# PWR_SRC.net
KiCad netlist of a schematic drawn in Altium Designer
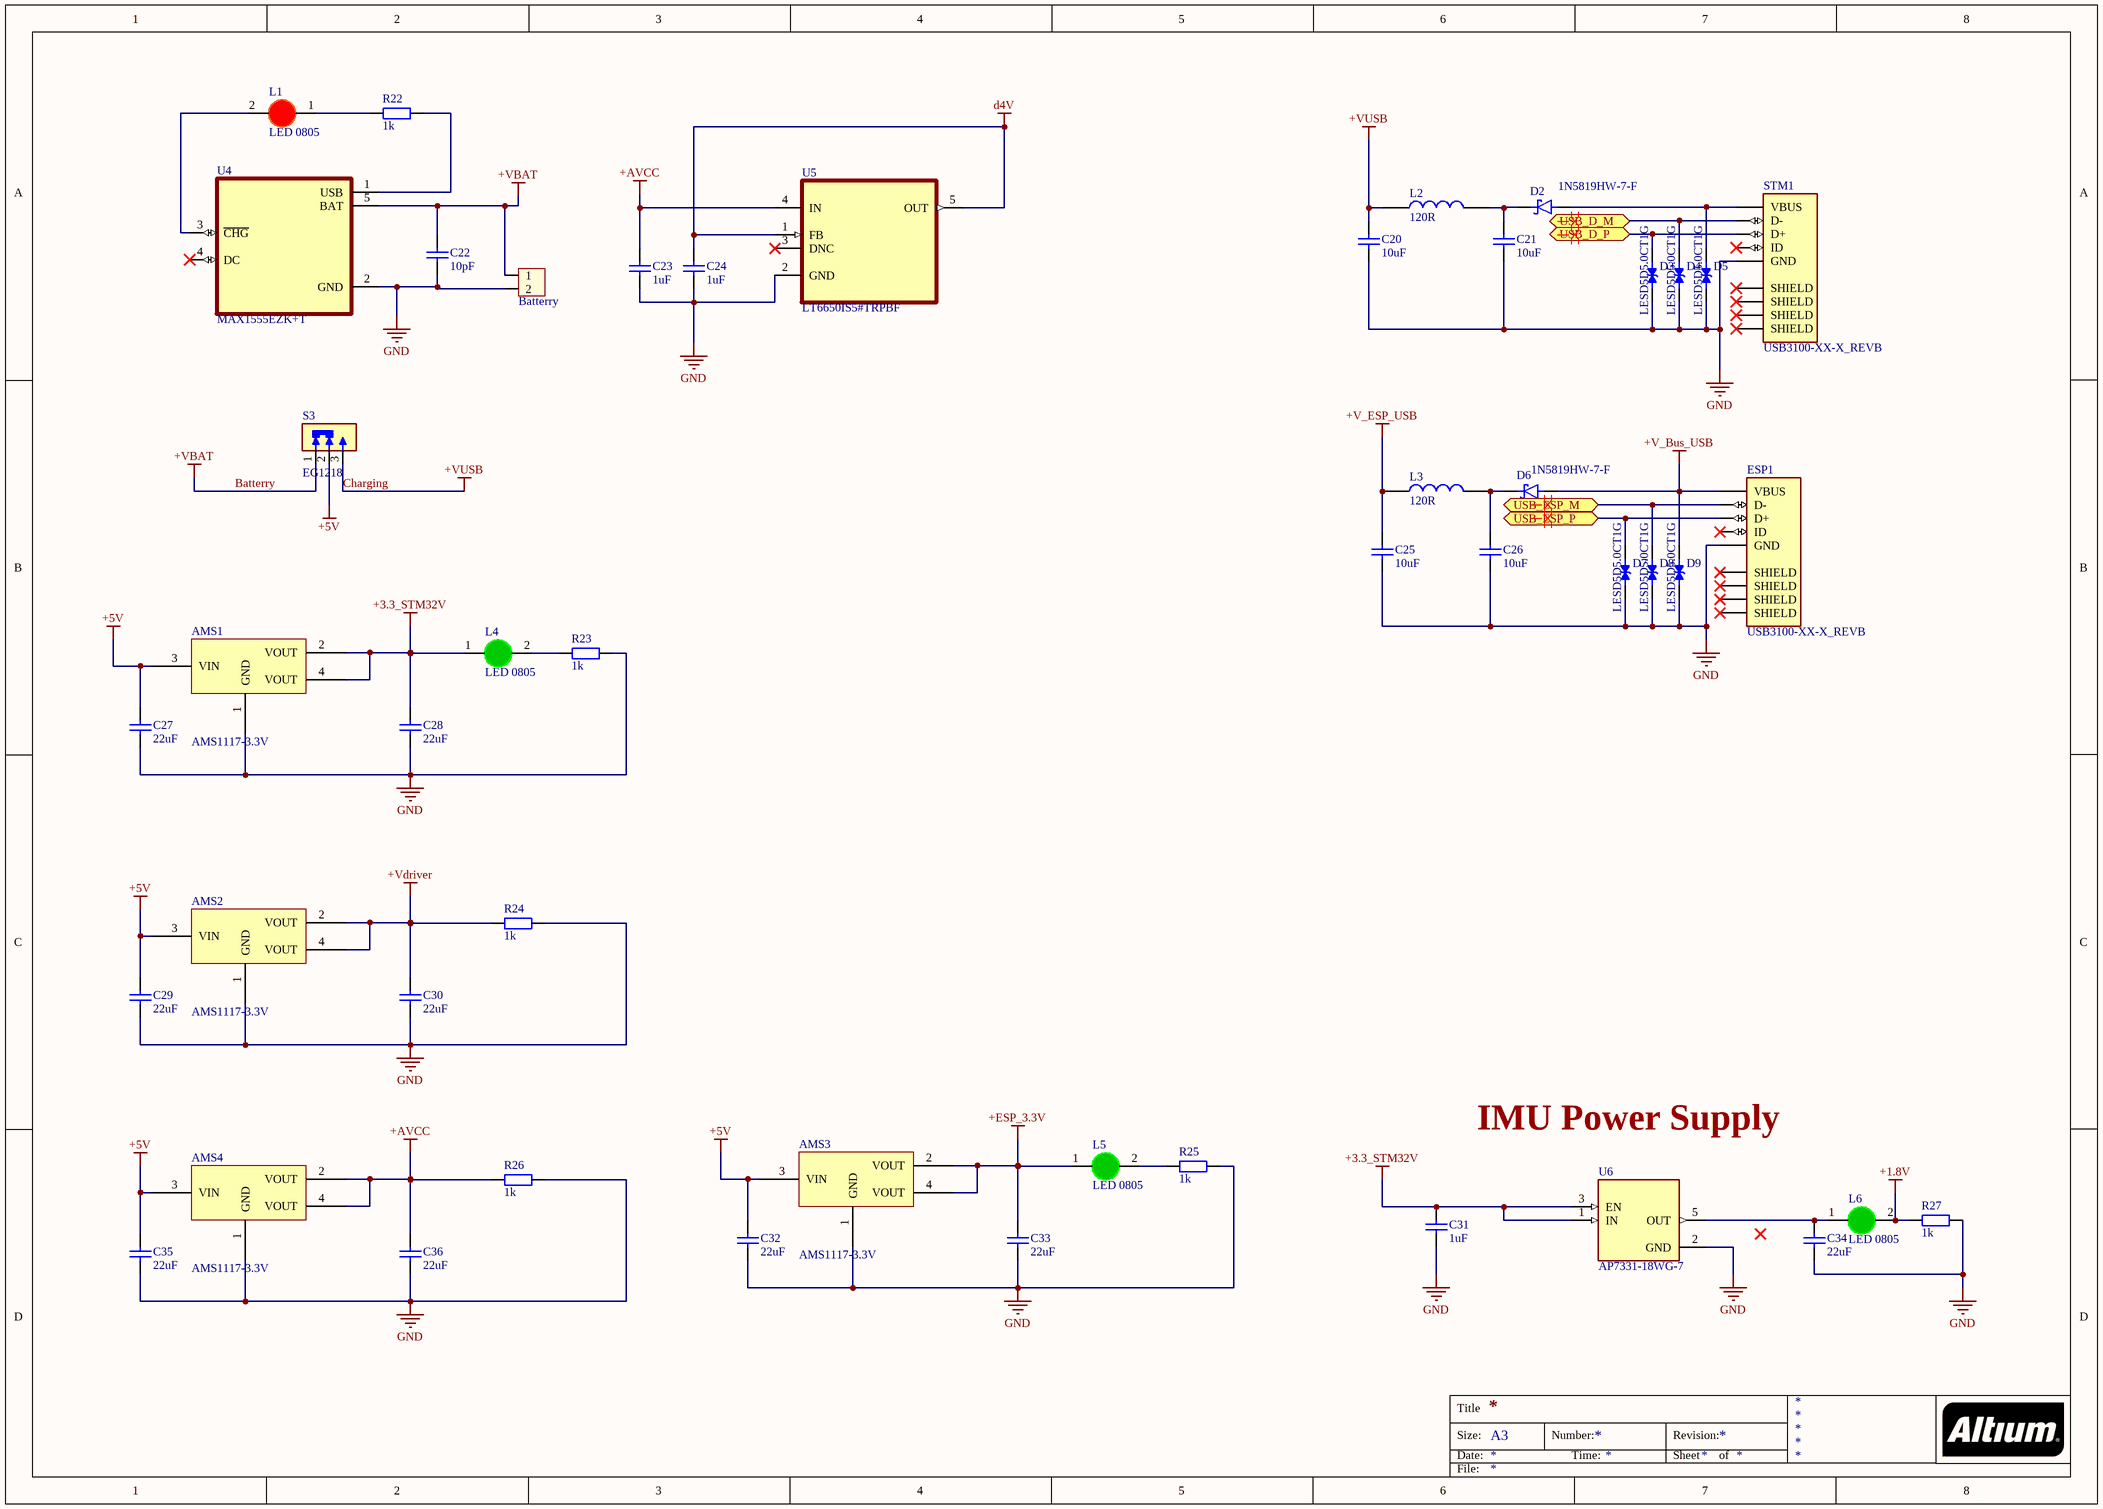
[diagram p0: PWR_SRC.SchDoc]

(export (version "E")
  (design (tool "Eeschema 10.0.6"))
  (components
    (comp (ref "AMS1")
      (value "AMS1117-3.3V")
      (footprint "SOT223")
      (description "Dán")
      (libsource (lib "Altium_Lib_by_KhueNguyenCreator") (part "AMS1117 SMD"))
    )
    (comp (ref "AMS2")
      (value "AMS1117-3.3V")
      (footprint "SOT223")
      (description "Dán")
      (libsource (lib "Altium_Lib_by_KhueNguyenCreator") (part "AMS1117 SMD"))
    )
    (comp (ref "AMS3")
      (value "AMS1117-3.3V")
      (footprint "SOT223")
      (description "Dán")
      (libsource (lib "Altium_Lib_by_KhueNguyenCreator") (part "AMS1117 SMD"))
    )
    (comp (ref "AMS4")
      (value "AMS1117-3.3V")
      (footprint "SOT223")
      (description "Dán")
      (libsource (lib "Altium_Lib_by_KhueNguyenCreator") (part "AMS1117 SMD"))
    )
    (comp (ref "Batterry1")
      (value "Batterry")
      (footprint "XH2.54M-2")
      (description "Cắm")
      (libsource (lib "Altium_Lib_by_KhueNguyenCreator") (part "Header 2P 2.54 Duc Thang"))
    )
    (comp (ref "C20")
      (value "10uF")
      (footprint "tu 0805")
      (description "Dán")
      (libsource (lib "Altium_Lib_by_KhueNguyenCreator") (part "Tu 0805 10pF 50V 10%"))
    )
    (comp (ref "C21")
      (value "10uF")
      (footprint "tu 0805")
      (description "Dán")
      (libsource (lib "Altium_Lib_by_KhueNguyenCreator") (part "Tu 0805 10pF 50V 10%"))
    )
    (comp (ref "C22")
      (value "10pF")
      (footprint "tu 0805")
      (description "Dán")
      (libsource (lib "Altium_Lib_by_KhueNguyenCreator") (part "Tu 0805 10pF 50V 10%"))
    )
    (comp (ref "C23")
      (value "1uF")
      (footprint "tu 0603")
      (description "Dán")
      (libsource (lib "Altium_Lib_by_KhueNguyenCreator") (part "Tu 0603 470pF 50V 10%"))
    )
    (comp (ref "C24")
      (value "1uF")
      (footprint "tu 0603")
      (description "Dán")
      (libsource (lib "Altium_Lib_by_KhueNguyenCreator") (part "Tu 0603 470pF 50V 10%"))
    )
    (comp (ref "C25")
      (value "10uF")
      (footprint "tu 0805")
      (description "Dán")
      (libsource (lib "Altium_Lib_by_KhueNguyenCreator") (part "Tu 0805 10pF 50V 10%"))
    )
    (comp (ref "C26")
      (value "10uF")
      (footprint "tu 0805")
      (description "Dán")
      (libsource (lib "Altium_Lib_by_KhueNguyenCreator") (part "Tu 0805 10pF 50V 10%"))
    )
    (comp (ref "C27")
      (value "22uF")
      (footprint "tu 0805")
      (description "Dán")
      (libsource (lib "Altium_Lib_by_KhueNguyenCreator") (part "Tu 0805 10pF 50V 10%"))
    )
    (comp (ref "C28")
      (value "22uF")
      (footprint "tu 0805")
      (description "Dán")
      (libsource (lib "Altium_Lib_by_KhueNguyenCreator") (part "Tu 0805 10pF 50V 10%"))
    )
    (comp (ref "C29")
      (value "22uF")
      (footprint "tu 0805")
      (description "Dán")
      (libsource (lib "Altium_Lib_by_KhueNguyenCreator") (part "Tu 0805 10pF 50V 10%"))
    )
    (comp (ref "C30")
      (value "22uF")
      (footprint "tu 0805")
      (description "Dán")
      (libsource (lib "Altium_Lib_by_KhueNguyenCreator") (part "Tu 0805 10pF 50V 10%"))
    )
    (comp (ref "C31")
      (value "1uF")
      (footprint "tu 0805")
      (description "Dán")
      (libsource (lib "Altium_Lib_by_KhueNguyenCreator") (part "Tu 0805 106 16V 10%"))
    )
    (comp (ref "C32")
      (value "22uF")
      (footprint "tu 0805")
      (description "Dán")
      (libsource (lib "Altium_Lib_by_KhueNguyenCreator") (part "Tu 0805 10pF 50V 10%"))
    )
    (comp (ref "C33")
      (value "22uF")
      (footprint "tu 0805")
      (description "Dán")
      (libsource (lib "Altium_Lib_by_KhueNguyenCreator") (part "Tu 0805 10pF 50V 10%"))
    )
    (comp (ref "C34")
      (value "22uF")
      (footprint "tu 0805")
      (description "Dán")
      (libsource (lib "Altium_Lib_by_KhueNguyenCreator") (part "Tu 0805 10pF 50V 10%"))
    )
    (comp (ref "C35")
      (value "22uF")
      (footprint "tu 0805")
      (description "Dán")
      (libsource (lib "Altium_Lib_by_KhueNguyenCreator") (part "Tu 0805 10pF 50V 10%"))
    )
    (comp (ref "C36")
      (value "22uF")
      (footprint "tu 0805")
      (description "Dán")
      (libsource (lib "Altium_Lib_by_KhueNguyenCreator") (part "Tu 0805 10pF 50V 10%"))
    )
    (comp (ref "D2")
      (value "1N5819HW-7-F")
      (footprint "1N5819HW-7-F:SOD3715X145N")
      (description "1N5819HW Series 40 V 1 A Surface Mount Schottky Barrier Rectifier - SOD-123")
      (fields (field (name "MF") "{'manufacturer': u'Diodes Inc.'}"))
      (libsource (lib "*") (part "1N5819HW-7-F"))
    )
    (comp (ref "D3")
      (value "LESD5D5.0CT1G")
      (footprint "LESD5D5.0CT1G:TVS_LESD5D5.0CT1G")
      (fields (field (name "MF") "{'manufacturer': u'Leshan Radio Co.'}"))
      (libsource (lib "*") (part "LESD5D5.0CT1G"))
    )
    (comp (ref "D4")
      (value "LESD5D5.0CT1G")
      (footprint "LESD5D5.0CT1G:TVS_LESD5D5.0CT1G")
      (fields (field (name "MF") "{'manufacturer': u'Leshan Radio Co.'}"))
      (libsource (lib "*") (part "LESD5D5.0CT1G"))
    )
    (comp (ref "D5")
      (value "LESD5D5.0CT1G")
      (footprint "LESD5D5.0CT1G:TVS_LESD5D5.0CT1G")
      (fields (field (name "MF") "{'manufacturer': u'Leshan Radio Co.'}"))
      (libsource (lib "*") (part "LESD5D5.0CT1G"))
    )
    (comp (ref "D6")
      (value "1N5819HW-7-F")
      (footprint "1N5819HW-7-F:SOD3715X145N")
      (description "1N5819HW Series 40 V 1 A Surface Mount Schottky Barrier Rectifier - SOD-123")
      (fields (field (name "MF") "{'manufacturer': u'Diodes Inc.'}"))
      (libsource (lib "*") (part "1N5819HW-7-F"))
    )
    (comp (ref "D7")
      (value "LESD5D5.0CT1G")
      (footprint "LESD5D5.0CT1G:TVS_LESD5D5.0CT1G")
      (fields (field (name "MF") "{'manufacturer': u'Leshan Radio Co.'}"))
      (libsource (lib "*") (part "LESD5D5.0CT1G"))
    )
    (comp (ref "D8")
      (value "LESD5D5.0CT1G")
      (footprint "LESD5D5.0CT1G:TVS_LESD5D5.0CT1G")
      (fields (field (name "MF") "{'manufacturer': u'Leshan Radio Co.'}"))
      (libsource (lib "*") (part "LESD5D5.0CT1G"))
    )
    (comp (ref "D9")
      (value "LESD5D5.0CT1G")
      (footprint "LESD5D5.0CT1G:TVS_LESD5D5.0CT1G")
      (fields (field (name "MF") "{'manufacturer': u'Leshan Radio Co.'}"))
      (libsource (lib "*") (part "LESD5D5.0CT1G"))
    )
    (comp (ref "ESP1")
      (value "USB3100-XX-X_REVB")
      (footprint "USB3100-30-A:GCT_USB3100-XX-X_REVB")
      (description "Micro USB Receptacle, Type B, Surface Mount, Horizontal, Top (Reverse) Mount, without Peg")
      (fields (field (name "MF") "{'manufacturer': u'Global Connector Technology'}"))
      (libsource (lib "*") (part "USB3100-XX-X_REVB"))
    )
    (comp (ref "L1")
      (value "LED 0805")
      (footprint "LED-1206-Red")
      (description "Dán")
      (libsource (lib "Altium_Lib_by_KhueNguyenCreator") (part "LED 1206 Do"))
    )
    (comp (ref "L2")
      (value "120R")
      (footprint "IND-0603 (1608)")
      (description "IND-FERRITE BEAD 23 OHM  4A 0603 1LN")
      (fields (field (name "MPN") "FBMJ1608HM230NT"))
      (libsource (lib "BYTECH_HW_LIB_2019 (1)") (part "FBMJ1608HM230NT"))
    )
    (comp (ref "L3")
      (value "120R")
      (footprint "IND-0603 (1608)")
      (description "IND-FERRITE BEAD 23 OHM  4A 0603 1LN")
      (fields (field (name "MPN") "FBMJ1608HM230NT"))
      (libsource (lib "BYTECH_HW_LIB_2019 (1)") (part "FBMJ1608HM230NT"))
    )
    (comp (ref "L4")
      (value "LED 0805")
      (footprint "LED-1206-Green")
      (description "Dán")
      (libsource (lib "Altium_Lib_by_KhueNguyenCreator") (part "LED 1206 Xanh La"))
    )
    (comp (ref "L5")
      (value "LED 0805")
      (footprint "LED-1206-Green")
      (description "Dán")
      (libsource (lib "Altium_Lib_by_KhueNguyenCreator") (part "LED 1206 Xanh La"))
    )
    (comp (ref "L6")
      (value "LED 0805")
      (footprint "LED-1206-Green")
      (description "Dán")
      (libsource (lib "Altium_Lib_by_KhueNguyenCreator") (part "LED 1206 Xanh La"))
    )
    (comp (ref "R22")
      (value "1k")
      (footprint "tro smd 0805")
      (description "Dán")
      (libsource (lib "Altium_Lib_by_KhueNguyenCreator") (part "Tro 0805 1% 1k"))
    )
    (comp (ref "R23")
      (value "1k")
      (footprint "tro smd 0805")
      (description "Dán")
      (libsource (lib "Altium_Lib_by_KhueNguyenCreator") (part "Tro 0805 1% 1k"))
    )
    (comp (ref "R24")
      (value "1k")
      (footprint "tro smd 0805")
      (description "Dán")
      (libsource (lib "Altium_Lib_by_KhueNguyenCreator") (part "Tro 0805 1% 1k"))
    )
    (comp (ref "R25")
      (value "1k")
      (footprint "tro smd 0805")
      (description "Dán")
      (libsource (lib "Altium_Lib_by_KhueNguyenCreator") (part "Tro 0805 1% 1k"))
    )
    (comp (ref "R26")
      (value "1k")
      (footprint "tro smd 0805")
      (description "Dán")
      (libsource (lib "Altium_Lib_by_KhueNguyenCreator") (part "Tro 0805 1% 1k"))
    )
    (comp (ref "R27")
      (value "1k")
      (footprint "tro smd 0805")
      (description "Dán")
      (libsource (lib "Altium_Lib_by_KhueNguyenCreator") (part "Tro 0805 1% 1k"))
    )
    (comp (ref "S3")
      (value "EG1218")
      (footprint "SW_EG1218")
      (description "Slide Switch, EG Series, SPDT, Non-Shorting, ON-ON, 200mA DC, 30VDC, PC Pin ¦ E-Switch EG1218")
      (fields (field (name "MF") "E-Switch"))
      (libsource (lib "EG1218") (part "EG1218"))
    )
    (comp (ref "STM1")
      (value "USB3100-XX-X_REVB")
      (footprint "USB3100-30-A:GCT_USB3100-XX-X_REVB")
      (description "Micro USB Receptacle, Type B, Surface Mount, Horizontal, Top (Reverse) Mount, without Peg")
      (fields (field (name "MF") "{'manufacturer': u'Global Connector Technology'}"))
      (libsource (lib "*") (part "USB3100-XX-X_REVB"))
    )
    (comp (ref "U4")
      (value "MAX1555EZK+T")
      (footprint "MAX1555EZK:SOT95P275X110-5N")
      (fields (field (name "MF") "{'manufacturer': u'Analog Devices'}") (field (name "MP") "MAX1555EZK+"))
      (libsource (lib "*") (part "MAX1555EZK+T"))
    )
    (comp (ref "U5")
      (value "LT6650IS5#TRPBF")
      (footprint "LT6650IS5#TRPBF:SOT95P280X100-5N")
      (description "Micropower, 400mV Reference with Rail-to-Rail Buffer Amplifier")
      (fields (field (name "MF") "{'manufacturer': u'Analog Devices'}"))
      (libsource (lib "*") (part "LT6650IS5#TRPBF"))
    )
    (comp (ref "U6")
      (value "AP7331-18WG-7")
      (footprint "AP7331-18WG-7:SOT95P285X145-5N")
      (description "LDO Regulator Pos 1.8V 0.3A 5-Pin SOT-25 T/R")
      (fields (field (name "MF") "{'manufacturer': u'Diodes Inc.'}"))
      (libsource (lib "*") (part "AP7331-18WG-7"))
    )
  )
  (nets
    (net (code "1") (name "+1.8V") (class "Default")
      (node (ref "L6") (pin "2") (pinfunction "K_2") (pintype "passive"))
      (node (ref "R27") (pin "1") (pinfunction "1_1") (pintype "passive"))
    )
    (net (code "2") (name "+3.3_STM32V") (class "Default")
      (node (ref "AMS1") (pin "2") (pinfunction "VOUT_2") (pintype "passive"))
      (node (ref "AMS1") (pin "4") (pinfunction "VOUT_4") (pintype "passive"))
      (node (ref "C28") (pin "1") (pinfunction "1_1") (pintype "passive"))
      (node (ref "C31") (pin "1") (pinfunction "1_1") (pintype "passive"))
      (node (ref "L4") (pin "1") (pinfunction "A_1") (pintype "passive"))
      (node (ref "U6") (pin "1") (pinfunction "IN_1") (pintype "input"))
      (node (ref "U6") (pin "3") (pinfunction "EN_3") (pintype "input"))
    )
    (net (code "3") (name "+5V") (class "Default")
      (node (ref "AMS1") (pin "3") (pinfunction "VIN_3") (pintype "passive"))
      (node (ref "AMS2") (pin "3") (pinfunction "VIN_3") (pintype "passive"))
      (node (ref "AMS3") (pin "3") (pinfunction "VIN_3") (pintype "passive"))
      (node (ref "AMS4") (pin "3") (pinfunction "VIN_3") (pintype "passive"))
      (node (ref "C27") (pin "1") (pinfunction "1_1") (pintype "passive"))
      (node (ref "C29") (pin "1") (pinfunction "1_1") (pintype "passive"))
      (node (ref "C32") (pin "1") (pinfunction "1_1") (pintype "passive"))
      (node (ref "C35") (pin "1") (pinfunction "1_1") (pintype "passive"))
      (node (ref "S3") (pin "2") (pinfunction "COM_2") (pintype "passive"))
    )
    (net (code "4") (name "+AVCC") (class "Default")
      (node (ref "AMS4") (pin "2") (pinfunction "VOUT_2") (pintype "passive"))
      (node (ref "AMS4") (pin "4") (pinfunction "VOUT_4") (pintype "passive"))
      (node (ref "C23") (pin "1") (pinfunction "1_1") (pintype "passive"))
      (node (ref "C36") (pin "1") (pinfunction "1_1") (pintype "passive"))
      (node (ref "R26") (pin "1") (pinfunction "1_1") (pintype "passive"))
      (node (ref "U5") (pin "4") (pinfunction "IN_4") (pintype "power_in"))
    )
    (net (code "5") (name "+ESP_3.3V") (class "Default")
      (node (ref "AMS3") (pin "2") (pinfunction "VOUT_2") (pintype "passive"))
      (node (ref "AMS3") (pin "4") (pinfunction "VOUT_4") (pintype "passive"))
      (node (ref "C33") (pin "1") (pinfunction "1_1") (pintype "passive"))
      (node (ref "L5") (pin "1") (pinfunction "A_1") (pintype "passive"))
    )
    (net (code "6") (name "+VBAT") (class "Default")
      (node (ref "Batterry1") (pin "1") (pinfunction "1_1") (pintype "passive"))
      (node (ref "C22") (pin "1") (pinfunction "1_1") (pintype "passive"))
      (node (ref "S3") (pin "1") (pinfunction "NC_1") (pintype "passive"))
      (node (ref "U4") (pin "5") (pinfunction "BAT_5") (pintype "power_in"))
    )
    (net (code "7") (name "+VUSB") (class "Default")
      (node (ref "C20") (pin "1") (pinfunction "1_1") (pintype "passive"))
      (node (ref "L2") (pin "1") (pinfunction "1_1") (pintype "passive"))
      (node (ref "S3") (pin "3") (pinfunction "NO_3") (pintype "passive"))
    )
    (net (code "8") (name "+V_Bus_USB") (class "Default")
      (node (ref "D6") (pin "A") (pinfunction "A_A") (pintype "passive"))
      (node (ref "D9") (pin "2") (pinfunction "2_2") (pintype "passive"))
      (node (ref "ESP1") (pin "1") (pinfunction "VBUS_1") (pintype "power_in"))
    )
    (net (code "9") (name "+V_ESP_USB") (class "Default")
      (node (ref "C25") (pin "1") (pinfunction "1_1") (pintype "passive"))
      (node (ref "L3") (pin "1") (pinfunction "1_1") (pintype "passive"))
    )
    (net (code "10") (name "+Vdriver") (class "Default")
      (node (ref "AMS2") (pin "2") (pinfunction "VOUT_2") (pintype "passive"))
      (node (ref "AMS2") (pin "4") (pinfunction "VOUT_4") (pintype "passive"))
      (node (ref "C30") (pin "1") (pinfunction "1_1") (pintype "passive"))
      (node (ref "R24") (pin "1") (pinfunction "1_1") (pintype "passive"))
    )
    (net (code "11") (name "/USB_D_M") (class "Default")
      (node (ref "D4") (pin "2") (pinfunction "2_2") (pintype "passive"))
      (node (ref "STM1") (pin "2") (pinfunction "D-_2") (pintype "bidirectional"))
    )
    (net (code "12") (name "/USB_D_P") (class "Default")
      (node (ref "D3") (pin "2") (pinfunction "2_2") (pintype "passive"))
      (node (ref "STM1") (pin "3") (pinfunction "D+_3") (pintype "bidirectional"))
    )
    (net (code "13") (name "/USB_ESP_M") (class "Default")
      (node (ref "D8") (pin "2") (pinfunction "2_2") (pintype "passive"))
      (node (ref "ESP1") (pin "2") (pinfunction "D-_2") (pintype "bidirectional"))
    )
    (net (code "14") (name "/USB_ESP_P") (class "Default")
      (node (ref "D7") (pin "2") (pinfunction "2_2") (pintype "passive"))
      (node (ref "ESP1") (pin "3") (pinfunction "D+_3") (pintype "bidirectional"))
    )
    (net (code "15") (name "GND") (class "Default")
      (node (ref "AMS1") (pin "1") (pinfunction "GND_1") (pintype "passive"))
      (node (ref "AMS2") (pin "1") (pinfunction "GND_1") (pintype "passive"))
      (node (ref "AMS3") (pin "1") (pinfunction "GND_1") (pintype "passive"))
      (node (ref "AMS4") (pin "1") (pinfunction "GND_1") (pintype "passive"))
      (node (ref "Batterry1") (pin "2") (pinfunction "2_2") (pintype "passive"))
      (node (ref "C20") (pin "2") (pinfunction "2_2") (pintype "passive"))
      (node (ref "C21") (pin "2") (pinfunction "2_2") (pintype "passive"))
      (node (ref "C22") (pin "2") (pinfunction "2_2") (pintype "passive"))
      (node (ref "C23") (pin "2") (pinfunction "2_2") (pintype "passive"))
      (node (ref "C24") (pin "2") (pinfunction "2_2") (pintype "passive"))
      (node (ref "C25") (pin "2") (pinfunction "2_2") (pintype "passive"))
      (node (ref "C26") (pin "2") (pinfunction "2_2") (pintype "passive"))
      (node (ref "C27") (pin "2") (pinfunction "2_2") (pintype "passive"))
      (node (ref "C28") (pin "2") (pinfunction "2_2") (pintype "passive"))
      (node (ref "C29") (pin "2") (pinfunction "2_2") (pintype "passive"))
      (node (ref "C30") (pin "2") (pinfunction "2_2") (pintype "passive"))
      (node (ref "C31") (pin "2") (pinfunction "2_2") (pintype "passive"))
      (node (ref "C32") (pin "2") (pinfunction "2_2") (pintype "passive"))
      (node (ref "C33") (pin "2") (pinfunction "2_2") (pintype "passive"))
      (node (ref "C34") (pin "2") (pinfunction "2_2") (pintype "passive"))
      (node (ref "C35") (pin "2") (pinfunction "2_2") (pintype "passive"))
      (node (ref "C36") (pin "2") (pinfunction "2_2") (pintype "passive"))
      (node (ref "D3") (pin "1") (pinfunction "1_1") (pintype "passive"))
      (node (ref "D4") (pin "1") (pinfunction "1_1") (pintype "passive"))
      (node (ref "D5") (pin "1") (pinfunction "1_1") (pintype "passive"))
      (node (ref "D7") (pin "1") (pinfunction "1_1") (pintype "passive"))
      (node (ref "D8") (pin "1") (pinfunction "1_1") (pintype "passive"))
      (node (ref "D9") (pin "1") (pinfunction "1_1") (pintype "passive"))
      (node (ref "ESP1") (pin "5") (pinfunction "GND_5") (pintype "power_in"))
      (node (ref "R23") (pin "2") (pinfunction "2_2") (pintype "passive"))
      (node (ref "R24") (pin "2") (pinfunction "2_2") (pintype "passive"))
      (node (ref "R25") (pin "2") (pinfunction "2_2") (pintype "passive"))
      (node (ref "R26") (pin "2") (pinfunction "2_2") (pintype "passive"))
      (node (ref "R27") (pin "2") (pinfunction "2_2") (pintype "passive"))
      (node (ref "STM1") (pin "5") (pinfunction "GND_5") (pintype "power_in"))
      (node (ref "U4") (pin "2") (pinfunction "GND_2") (pintype "power_in"))
      (node (ref "U5") (pin "2") (pinfunction "GND_2") (pintype "passive"))
      (node (ref "U6") (pin "2") (pinfunction "GND_2") (pintype "power_in"))
    )
    (net (code "16") (name "Net-(D2-K)") (class "Default")
      (node (ref "C21") (pin "1") (pinfunction "1_1") (pintype "passive"))
      (node (ref "D2") (pin "C") (pinfunction "K_C") (pintype "passive"))
      (node (ref "L2") (pin "2") (pinfunction "2_2") (pintype "passive"))
    )
    (net (code "17") (name "Net-(D6-K)") (class "Default")
      (node (ref "C26") (pin "1") (pinfunction "1_1") (pintype "passive"))
      (node (ref "D6") (pin "C") (pinfunction "K_C") (pintype "passive"))
      (node (ref "L3") (pin "2") (pinfunction "2_2") (pintype "passive"))
    )
    (net (code "18") (name "Net-(L1-A)") (class "Default")
      (node (ref "L1") (pin "1") (pinfunction "A_1") (pintype "passive"))
      (node (ref "R22") (pin "1") (pinfunction "1_1") (pintype "passive"))
    )
    (net (code "19") (name "Net-(L1-K)") (class "Default")
      (node (ref "L1") (pin "2") (pinfunction "K_2") (pintype "passive"))
      (node (ref "U4") (pin "3") (pinfunction "~{CHG}_3") (pintype "bidirectional"))
    )
    (net (code "20") (name "Net-(L4-K)") (class "Default")
      (node (ref "L4") (pin "2") (pinfunction "K_2") (pintype "passive"))
      (node (ref "R23") (pin "1") (pinfunction "1_1") (pintype "passive"))
    )
    (net (code "21") (name "Net-(L5-K)") (class "Default")
      (node (ref "L5") (pin "2") (pinfunction "K_2") (pintype "passive"))
      (node (ref "R25") (pin "1") (pinfunction "1_1") (pintype "passive"))
    )
    (net (code "22") (name "Net-(L6-A)") (class "Default")
      (node (ref "C34") (pin "1") (pinfunction "1_1") (pintype "passive"))
      (node (ref "L6") (pin "1") (pinfunction "A_1") (pintype "passive"))
      (node (ref "U6") (pin "5") (pinfunction "OUT_5") (pintype "output"))
    )
    (net (code "23") (name "Net-(STM1-VBUS)") (class "Default")
      (node (ref "D2") (pin "A") (pinfunction "A_A") (pintype "passive"))
      (node (ref "D5") (pin "2") (pinfunction "2_2") (pintype "passive"))
      (node (ref "STM1") (pin "1") (pinfunction "VBUS_1") (pintype "power_in"))
    )
    (net (code "24") (name "Net-(U4-USB)") (class "Default")
      (node (ref "R22") (pin "2") (pinfunction "2_2") (pintype "passive"))
      (node (ref "U4") (pin "1") (pinfunction "USB_1") (pintype "power_in"))
    )
    (net (code "25") (name "d4V") (class "Default")
      (node (ref "C24") (pin "1") (pinfunction "1_1") (pintype "passive"))
      (node (ref "U5") (pin "1") (pinfunction "FB_1") (pintype "input"))
      (node (ref "U5") (pin "5") (pinfunction "OUT_5") (pintype "output"))
    )
    (net (code "26") (name "unconnected-(ESP1-ID-Pad4)") (class "Default")
      (node (ref "ESP1") (pin "4") (pinfunction "ID_4") (pintype "bidirectional+no_connect"))
    )
    (net (code "27") (name "unconnected-(ESP1-SHIELD-Pad6)") (class "Default")
      (node (ref "ESP1") (pin "6") (pinfunction "SHIELD_6") (pintype "power_in+no_connect"))
    )
    (net (code "28") (name "unconnected-(ESP1-SHIELD-Pad7)") (class "Default")
      (node (ref "ESP1") (pin "7") (pinfunction "SHIELD_7") (pintype "power_in+no_connect"))
    )
    (net (code "29") (name "unconnected-(ESP1-SHIELD-Pad8)") (class "Default")
      (node (ref "ESP1") (pin "8") (pinfunction "SHIELD_8") (pintype "power_in+no_connect"))
    )
    (net (code "30") (name "unconnected-(ESP1-SHIELD-Pad9)") (class "Default")
      (node (ref "ESP1") (pin "9") (pinfunction "SHIELD_9") (pintype "power_in+no_connect"))
    )
    (net (code "31") (name "unconnected-(STM1-ID-Pad4)") (class "Default")
      (node (ref "STM1") (pin "4") (pinfunction "ID_4") (pintype "bidirectional+no_connect"))
    )
    (net (code "32") (name "unconnected-(STM1-SHIELD-Pad6)") (class "Default")
      (node (ref "STM1") (pin "6") (pinfunction "SHIELD_6") (pintype "power_in+no_connect"))
    )
    (net (code "33") (name "unconnected-(STM1-SHIELD-Pad7)") (class "Default")
      (node (ref "STM1") (pin "7") (pinfunction "SHIELD_7") (pintype "power_in+no_connect"))
    )
    (net (code "34") (name "unconnected-(STM1-SHIELD-Pad8)") (class "Default")
      (node (ref "STM1") (pin "8") (pinfunction "SHIELD_8") (pintype "power_in+no_connect"))
    )
    (net (code "35") (name "unconnected-(STM1-SHIELD-Pad9)") (class "Default")
      (node (ref "STM1") (pin "9") (pinfunction "SHIELD_9") (pintype "power_in+no_connect"))
    )
    (net (code "36") (name "unconnected-(U4-DC-Pad4)") (class "Default")
      (node (ref "U4") (pin "4") (pinfunction "DC_4") (pintype "bidirectional+no_connect"))
    )
    (net (code "37") (name "unconnected-(U5-DNC-Pad3)") (class "Default")
      (node (ref "U5") (pin "3") (pinfunction "DNC_3") (pintype "passive+no_connect"))
    )
  )
)
